# powerOutageLogger.net
KiCad netlist of a schematic drawn in EAGLE
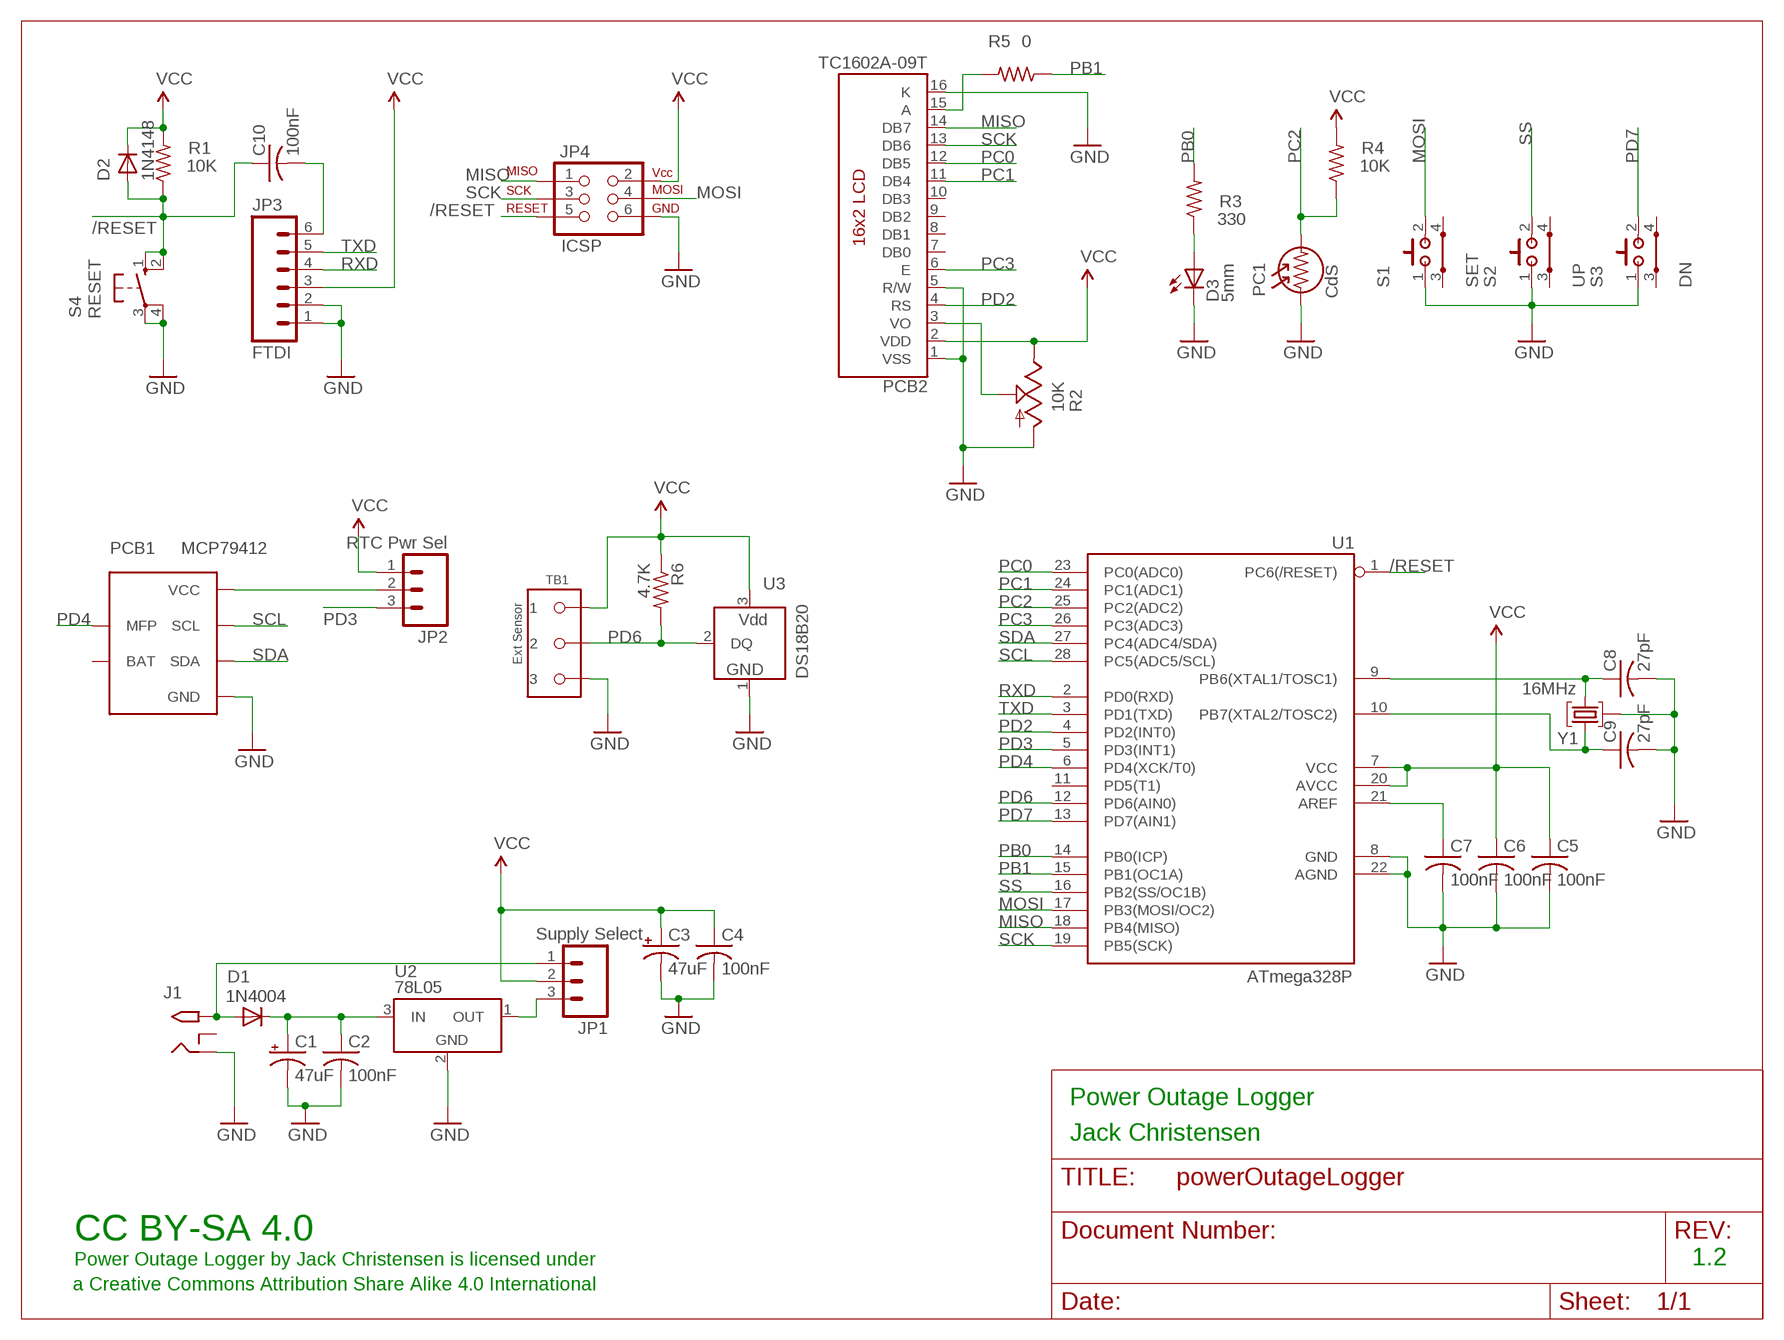
[diagram p0: schematic, sheet 1]

(export (version "E")
  (design (tool "Eeschema 10.0.6"))
  (components
    (comp (ref "C1")
      (value "47uF")
      (footprint "eagle-import:E2-5")
      (libsource (lib "eagle-import") (part "CPOL-USE2-5"))
    )
    (comp (ref "C2")
      (value "100nF")
      (footprint "eagle-import:C025-025X050")
      (libsource (lib "eagle-import") (part "C-US025-025X050"))
    )
    (comp (ref "C3")
      (value "47uF")
      (footprint "eagle-import:E2-5")
      (libsource (lib "eagle-import") (part "CPOL-USE2-5"))
    )
    (comp (ref "C4")
      (value "100nF")
      (footprint "eagle-import:C025-025X050")
      (libsource (lib "eagle-import") (part "C-US025-025X050"))
    )
    (comp (ref "C5")
      (value "100nF")
      (footprint "eagle-import:C025-025X050")
      (libsource (lib "eagle-import") (part "C-US025-025X050"))
    )
    (comp (ref "C6")
      (value "100nF")
      (footprint "eagle-import:C025-025X050")
      (libsource (lib "eagle-import") (part "C-US025-025X050"))
    )
    (comp (ref "C7")
      (value "100nF")
      (footprint "eagle-import:C025-025X050")
      (libsource (lib "eagle-import") (part "C-US025-025X050"))
    )
    (comp (ref "C8")
      (value "27pF")
      (footprint "eagle-import:C025-025X050")
      (libsource (lib "eagle-import") (part "C-US025-025X050"))
    )
    (comp (ref "C9")
      (value "27pF")
      (footprint "eagle-import:C025-025X050")
      (libsource (lib "eagle-import") (part "C-US025-025X050"))
    )
    (comp (ref "C10")
      (value "100nF")
      (footprint "eagle-import:C025-025X050")
      (libsource (lib "eagle-import") (part "C-US025-025X050"))
    )
    (comp (ref "D1")
      (value "1N4004")
      (footprint "eagle-import:1N400X")
      (libsource (lib "eagle-import") (part "DIODE1N400X"))
    )
    (comp (ref "D2")
      (value "1N4148")
      (footprint "eagle-import:1N4148")
      (libsource (lib "eagle-import") (part "DIODE1N4148"))
    )
    (comp (ref "D3")
      (value "5mm")
      (footprint "eagle-import:LED5MM")
      (libsource (lib "eagle-import") (part "LED5MM"))
    )
    (comp (ref "J1")
      (value "2.1MMJACKTHM")
      (footprint "eagle-import:PJ-102A")
      (libsource (lib "eagle-import") (part "2.1MMJACKTHM"))
    )
    (comp (ref "JP1")
      (value "Supply Select")
      (footprint "eagle-import:1X03_LOCK")
      (libsource (lib "eagle-import") (part "M03LOCK"))
    )
    (comp (ref "JP2")
      (value "RTC Pwr Sel")
      (footprint "eagle-import:1X03_LOCK")
      (libsource (lib "eagle-import") (part "M03LOCK"))
    )
    (comp (ref "JP3")
      (value "FTDI")
      (footprint "eagle-import:1X06_LOCK")
      (libsource (lib "eagle-import") (part "M06LOCK"))
    )
    (comp (ref "JP4")
      (value "ICSP")
      (footprint "eagle-import:2X3")
      (libsource (lib "eagle-import") (part "AVR_SPI_PRG_6PTH"))
    )
    (comp (ref "PC1")
      (value "CdS")
      (footprint "eagle-import:PHOTOCELL-020-017")
      (libsource (lib "eagle-import") (part "PHOTOCELL020-017"))
    )
    (comp (ref "PCB1")
      (value "MCP79412")
      (footprint "eagle-import:RTC79412")
      (libsource (lib "eagle-import") (part "RTC79412"))
    )
    (comp (ref "PCB2")
      (value "TC1602A-09T")
      (footprint "eagle-import:LCD-16X2")
      (libsource (lib "eagle-import") (part "LCD-16X2"))
    )
    (comp (ref "R1")
      (value "10K")
      (footprint "eagle-import:0204_6")
      (libsource (lib "eagle-import") (part "R-US_0204/6"))
    )
    (comp (ref "R2")
      (value "10K")
      (footprint "eagle-import:TRIMPOT-3386P")
      (libsource (lib "eagle-import") (part "TRIMPOT-3386P3386P"))
    )
    (comp (ref "R3")
      (value "330")
      (footprint "eagle-import:0204_6")
      (libsource (lib "eagle-import") (part "R-US_0204/6"))
    )
    (comp (ref "R4")
      (value "10K")
      (footprint "eagle-import:0204_6")
      (libsource (lib "eagle-import") (part "R-US_0204/6"))
    )
    (comp (ref "R5")
      (value "0")
      (footprint "eagle-import:0204_6")
      (libsource (lib "eagle-import") (part "R-US_0204/6"))
    )
    (comp (ref "R6")
      (value "4.7K")
      (footprint "eagle-import:0204_6")
      (libsource (lib "eagle-import") (part "R-US_0204/6"))
    )
    (comp (ref "S1")
      (value "SET")
      (footprint "eagle-import:B3F-312X")
      (libsource (lib "eagle-import") (part "B3F-312X"))
    )
    (comp (ref "S2")
      (value "UP")
      (footprint "eagle-import:B3F-312X")
      (libsource (lib "eagle-import") (part "B3F-312X"))
    )
    (comp (ref "S3")
      (value "DN")
      (footprint "eagle-import:B3F-312X")
      (libsource (lib "eagle-import") (part "B3F-312X"))
    )
    (comp (ref "S4")
      (value "RESET")
      (footprint "eagle-import:B3F-10XXOCT")
      (libsource (lib "eagle-import") (part "10-XXOCT"))
    )
    (comp (ref "TB1")
      (value "Ext Sensor")
      (footprint "eagle-import:OST-TB-3-3.5MM")
      (libsource (lib "eagle-import") (part "OST-TB-33.5MM"))
    )
    (comp (ref "U1")
      (value "ATmega328P")
      (footprint "eagle-import:DIL28-3")
      (libsource (lib "eagle-import") (part "AVR-MEGA8-PPTH"))
    )
    (comp (ref "U2")
      (value "78L05")
      (footprint "eagle-import:TO92-INLINE")
      (libsource (lib "eagle-import") (part "78XX-HTO92"))
    )
    (comp (ref "U3")
      (value "DS18B20")
      (footprint "eagle-import:TO92-OVAL")
      (libsource (lib "eagle-import") (part "DS18B20"))
    )
    (comp (ref "Y1")
      (value "16MHz")
      (footprint "eagle-import:RESONATOR")
      (libsource (lib "eagle-import") (part "RESONATOR"))
    )
  )
  (nets
    (net (code "1") (name "/MISO") (class "Default")
      (node (ref "JP4") (pin "1") (pinfunction "1_1") (pintype "passive"))
      (node (ref "PCB2") (pin "14") (pinfunction "DB7_14") (pintype "bidirectional"))
      (node (ref "U1") (pin "18") (pinfunction "PB4(MISO)_18") (pintype "bidirectional"))
    )
    (net (code "2") (name "/MOSI") (class "Default")
      (node (ref "JP4") (pin "4") (pinfunction "4_4") (pintype "passive"))
      (node (ref "S1") (pin "2") (pinfunction "P$2_2") (pintype "passive"))
      (node (ref "U1") (pin "17") (pinfunction "PB3(MOSI/OC2)_17") (pintype "bidirectional"))
    )
    (net (code "3") (name "/PB0") (class "Default")
      (node (ref "R3") (pin "2") (pinfunction "2_2") (pintype "passive"))
      (node (ref "U1") (pin "14") (pinfunction "PB0(ICP)_14") (pintype "bidirectional"))
    )
    (net (code "4") (name "/PB1") (class "Default")
      (node (ref "R5") (pin "1") (pinfunction "1_1") (pintype "passive"))
      (node (ref "U1") (pin "15") (pinfunction "PB1(OC1A)_15") (pintype "bidirectional"))
    )
    (net (code "5") (name "/PC0") (class "Default")
      (node (ref "PCB2") (pin "12") (pinfunction "DB5_12") (pintype "bidirectional"))
      (node (ref "U1") (pin "23") (pinfunction "PC0(ADC0)_23") (pintype "bidirectional"))
    )
    (net (code "6") (name "/PC1") (class "Default")
      (node (ref "PCB2") (pin "11") (pinfunction "DB4_11") (pintype "bidirectional"))
      (node (ref "U1") (pin "24") (pinfunction "PC1(ADC1)_24") (pintype "bidirectional"))
    )
    (net (code "7") (name "/PC2") (class "Default")
      (node (ref "PC1") (pin "P$2") (pinfunction "2_P$2") (pintype "passive"))
      (node (ref "R4") (pin "1") (pinfunction "1_1") (pintype "passive"))
      (node (ref "U1") (pin "25") (pinfunction "PC2(ADC2)_25") (pintype "bidirectional"))
    )
    (net (code "8") (name "/PC3") (class "Default")
      (node (ref "PCB2") (pin "6") (pinfunction "E_6") (pintype "input"))
      (node (ref "U1") (pin "26") (pinfunction "PC3(ADC3)_26") (pintype "bidirectional"))
    )
    (net (code "9") (name "/PD2") (class "Default")
      (node (ref "PCB2") (pin "4") (pinfunction "RS_4") (pintype "input"))
      (node (ref "U1") (pin "4") (pinfunction "PD2(INT0)_4") (pintype "bidirectional"))
    )
    (net (code "10") (name "/PD3") (class "Default")
      (node (ref "JP2") (pin "3") (pinfunction "3_3") (pintype "passive"))
      (node (ref "U1") (pin "5") (pinfunction "PD3(INT1)_5") (pintype "bidirectional"))
    )
    (net (code "11") (name "/PD4") (class "Default")
      (node (ref "PCB1") (pin "3") (pinfunction "MFP_3") (pintype "passive"))
      (node (ref "U1") (pin "6") (pinfunction "PD4(XCK/T0)_6") (pintype "bidirectional"))
    )
    (net (code "12") (name "/PD6") (class "Default")
      (node (ref "R6") (pin "2") (pinfunction "2_2") (pintype "passive"))
      (node (ref "TB1") (pin "P$2") (pinfunction "2_P$2") (pintype "passive"))
      (node (ref "U1") (pin "12") (pinfunction "PD6(AIN0)_12") (pintype "bidirectional"))
      (node (ref "U3") (pin "2") (pinfunction "DQ_2") (pintype "bidirectional"))
    )
    (net (code "13") (name "/PD7") (class "Default")
      (node (ref "S3") (pin "2") (pinfunction "P$2_2") (pintype "passive"))
      (node (ref "U1") (pin "13") (pinfunction "PD7(AIN1)_13") (pintype "bidirectional"))
    )
    (net (code "14") (name "/RXD") (class "Default")
      (node (ref "JP3") (pin "4") (pinfunction "4_4") (pintype "passive"))
      (node (ref "U1") (pin "2") (pinfunction "PD0(RXD)_2") (pintype "bidirectional"))
    )
    (net (code "15") (name "/SCK") (class "Default")
      (node (ref "JP4") (pin "3") (pinfunction "3_3") (pintype "passive"))
      (node (ref "PCB2") (pin "13") (pinfunction "DB6_13") (pintype "bidirectional"))
      (node (ref "U1") (pin "19") (pinfunction "PB5(SCK)_19") (pintype "bidirectional"))
    )
    (net (code "16") (name "/SCL") (class "Default")
      (node (ref "PCB1") (pin "6") (pinfunction "SCL_6") (pintype "passive"))
      (node (ref "U1") (pin "28") (pinfunction "PC5(ADC5/SCL)_28") (pintype "bidirectional"))
    )
    (net (code "17") (name "/SDA") (class "Default")
      (node (ref "PCB1") (pin "5") (pinfunction "SDA_5") (pintype "passive"))
      (node (ref "U1") (pin "27") (pinfunction "PC4(ADC4/SDA)_27") (pintype "bidirectional"))
    )
    (net (code "18") (name "/SS") (class "Default")
      (node (ref "S2") (pin "2") (pinfunction "P$2_2") (pintype "passive"))
      (node (ref "U1") (pin "16") (pinfunction "PB2(SS/OC1B)_16") (pintype "bidirectional"))
    )
    (net (code "19") (name "/TXD") (class "Default")
      (node (ref "JP3") (pin "5") (pinfunction "5_5") (pintype "passive"))
      (node (ref "U1") (pin "3") (pinfunction "PD1(TXD)_3") (pintype "bidirectional"))
    )
    (net (code "20") (name "/{slash}RESET") (class "Default")
      (node (ref "C10") (pin "1") (pinfunction "1_1") (pintype "passive"))
      (node (ref "D2") (pin "A") (pinfunction "A_A") (pintype "passive"))
      (node (ref "JP4") (pin "5") (pinfunction "5_5") (pintype "passive"))
      (node (ref "R1") (pin "1") (pinfunction "1_1") (pintype "passive"))
      (node (ref "S4") (pin "1") (pinfunction "S_1") (pintype "passive"))
      (node (ref "S4") (pin "2") (pinfunction "S1_2") (pintype "passive"))
      (node (ref "U1") (pin "1") (pinfunction "PC6(/RESET)_1") (pintype "bidirectional"))
    )
    (net (code "21") (name "GND") (class "Default")
      (node (ref "C1") (pin "-") (pinfunction "-_-") (pintype "passive"))
      (node (ref "C2") (pin "2") (pinfunction "2_2") (pintype "passive"))
      (node (ref "C3") (pin "-") (pinfunction "-_-") (pintype "passive"))
      (node (ref "C4") (pin "2") (pinfunction "2_2") (pintype "passive"))
      (node (ref "C5") (pin "2") (pinfunction "2_2") (pintype "passive"))
      (node (ref "C6") (pin "2") (pinfunction "2_2") (pintype "passive"))
      (node (ref "C7") (pin "2") (pinfunction "2_2") (pintype "passive"))
      (node (ref "C8") (pin "2") (pinfunction "2_2") (pintype "passive"))
      (node (ref "C9") (pin "2") (pinfunction "2_2") (pintype "passive"))
      (node (ref "D3") (pin "K") (pinfunction "C_K") (pintype "passive"))
      (node (ref "J1") (pin "RING") (pinfunction "RING_RING") (pintype "bidirectional"))
      (node (ref "JP3") (pin "1") (pinfunction "1_1") (pintype "passive"))
      (node (ref "JP3") (pin "2") (pinfunction "2_2") (pintype "passive"))
      (node (ref "JP4") (pin "6") (pinfunction "6_6") (pintype "passive"))
      (node (ref "PC1") (pin "P$1") (pinfunction "1_P$1") (pintype "passive"))
      (node (ref "PCB1") (pin "8") (pinfunction "GND_8") (pintype "passive"))
      (node (ref "PCB2") (pin "1") (pinfunction "VSS_1") (pintype "power_in"))
      (node (ref "PCB2") (pin "16") (pinfunction "K_16") (pintype "power_in"))
      (node (ref "PCB2") (pin "5") (pinfunction "R/W_5") (pintype "input"))
      (node (ref "R2") (pin "3") (pinfunction "A_3") (pintype "passive"))
      (node (ref "S1") (pin "1") (pinfunction "P$1_1") (pintype "passive"))
      (node (ref "S2") (pin "1") (pinfunction "P$1_1") (pintype "passive"))
      (node (ref "S3") (pin "1") (pinfunction "P$1_1") (pintype "passive"))
      (node (ref "S4") (pin "3") (pinfunction "P_3") (pintype "passive"))
      (node (ref "S4") (pin "4") (pinfunction "P1_4") (pintype "passive"))
      (node (ref "TB1") (pin "P$3") (pinfunction "3_P$3") (pintype "passive"))
      (node (ref "U1") (pin "22") (pinfunction "AGND_22") (pintype "bidirectional"))
      (node (ref "U1") (pin "8") (pinfunction "GND_8") (pintype "bidirectional"))
      (node (ref "U2") (pin "2") (pinfunction "GND_2") (pintype "power_in"))
      (node (ref "U3") (pin "1") (pinfunction "GND_1") (pintype "bidirectional"))
      (node (ref "Y1") (pin "2") (pinfunction "2_2") (pintype "passive"))
    )
    (net (code "22") (name "Net-(C10-Pad2)") (class "Default")
      (node (ref "C10") (pin "2") (pinfunction "2_2") (pintype "passive"))
      (node (ref "JP3") (pin "6") (pinfunction "6_6") (pintype "passive"))
    )
    (net (code "23") (name "Net-(D1-PadA)") (class "Default")
      (node (ref "D1") (pin "A") (pinfunction "A_A") (pintype "passive"))
      (node (ref "J1") (pin "TIP") (pinfunction "TIP_TIP") (pintype "bidirectional"))
      (node (ref "JP1") (pin "1") (pinfunction "1_1") (pintype "passive"))
    )
    (net (code "24") (name "Net-(D3-PadA)") (class "Default")
      (node (ref "D3") (pin "A") (pinfunction "A_A") (pintype "passive"))
      (node (ref "R3") (pin "1") (pinfunction "1_1") (pintype "passive"))
    )
    (net (code "25") (name "Net-(PCB1-VCC)") (class "Default")
      (node (ref "JP2") (pin "2") (pinfunction "2_2") (pintype "passive"))
      (node (ref "PCB1") (pin "7") (pinfunction "VCC_7") (pintype "passive"))
    )
    (net (code "26") (name "Net-(PCB2-A)") (class "Default")
      (node (ref "PCB2") (pin "15") (pinfunction "A_15") (pintype "power_in"))
      (node (ref "R5") (pin "2") (pinfunction "2_2") (pintype "passive"))
    )
    (net (code "27") (name "Net-(PCB2-VO)") (class "Default")
      (node (ref "PCB2") (pin "3") (pinfunction "VO_3") (pintype "bidirectional"))
      (node (ref "R2") (pin "2") (pinfunction "S_2") (pintype "passive"))
    )
    (net (code "28") (name "Net-(U1-AREF)") (class "Default")
      (node (ref "C7") (pin "1") (pinfunction "1_1") (pintype "passive"))
      (node (ref "U1") (pin "21") (pinfunction "AREF_21") (pintype "bidirectional"))
    )
    (net (code "29") (name "Net-(U1-PB6(XTAL1{slash}TOSC1))") (class "Default")
      (node (ref "C8") (pin "1") (pinfunction "1_1") (pintype "passive"))
      (node (ref "U1") (pin "9") (pinfunction "PB6(XTAL1/TOSC1)_9") (pintype "bidirectional"))
      (node (ref "Y1") (pin "3") (pinfunction "3_3") (pintype "passive"))
    )
    (net (code "30") (name "Net-(U1-PB7(XTAL2{slash}TOSC2))") (class "Default")
      (node (ref "C9") (pin "1") (pinfunction "1_1") (pintype "passive"))
      (node (ref "U1") (pin "10") (pinfunction "PB7(XTAL2/TOSC2)_10") (pintype "bidirectional"))
      (node (ref "Y1") (pin "1") (pinfunction "1_1") (pintype "passive"))
    )
    (net (code "31") (name "Net-(U2-IN)") (class "Default")
      (node (ref "C1") (pin "+") (pinfunction "+_+") (pintype "passive"))
      (node (ref "C2") (pin "1") (pinfunction "1_1") (pintype "passive"))
      (node (ref "D1") (pin "K") (pinfunction "K_K") (pintype "passive"))
      (node (ref "U2") (pin "3") (pinfunction "IN_3") (pintype "input"))
    )
    (net (code "32") (name "Net-(U2-OUT)") (class "Default")
      (node (ref "JP1") (pin "3") (pinfunction "3_3") (pintype "passive"))
      (node (ref "U2") (pin "1") (pinfunction "OUT_1") (pintype "power_in"))
    )
    (net (code "33") (name "VCC") (class "Default")
      (node (ref "C3") (pin "+") (pinfunction "+_+") (pintype "passive"))
      (node (ref "C4") (pin "1") (pinfunction "1_1") (pintype "passive"))
      (node (ref "C5") (pin "1") (pinfunction "1_1") (pintype "passive"))
      (node (ref "C6") (pin "1") (pinfunction "1_1") (pintype "passive"))
      (node (ref "D2") (pin "K") (pinfunction "K_K") (pintype "passive"))
      (node (ref "JP1") (pin "2") (pinfunction "2_2") (pintype "passive"))
      (node (ref "JP2") (pin "1") (pinfunction "1_1") (pintype "passive"))
      (node (ref "JP3") (pin "3") (pinfunction "3_3") (pintype "passive"))
      (node (ref "JP4") (pin "2") (pinfunction "2_2") (pintype "passive"))
      (node (ref "PCB2") (pin "2") (pinfunction "VDD_2") (pintype "power_in"))
      (node (ref "R1") (pin "2") (pinfunction "2_2") (pintype "passive"))
      (node (ref "R2") (pin "1") (pinfunction "E_1") (pintype "passive"))
      (node (ref "R4") (pin "2") (pinfunction "2_2") (pintype "passive"))
      (node (ref "R6") (pin "1") (pinfunction "1_1") (pintype "passive"))
      (node (ref "TB1") (pin "P$1") (pinfunction "1_P$1") (pintype "passive"))
      (node (ref "U1") (pin "20") (pinfunction "AVCC_20") (pintype "bidirectional"))
      (node (ref "U1") (pin "7") (pinfunction "VCC_7") (pintype "bidirectional"))
      (node (ref "U3") (pin "3") (pinfunction "VDD_3") (pintype "bidirectional"))
    )
    (net (code "34") (name "unconnected-(J1-PadRING_SW)") (class "Default")
      (node (ref "J1") (pin "RING_SW") (pinfunction "RING_SW_RING_SW") (pintype "bidirectional"))
    )
    (net (code "35") (name "unconnected-(PCB1-BAT-Pad1)") (class "Default")
      (node (ref "PCB1") (pin "1") (pinfunction "BAT_1") (pintype "passive"))
    )
    (net (code "36") (name "unconnected-(PCB2-DB0-Pad7)") (class "Default")
      (node (ref "PCB2") (pin "7") (pinfunction "DB0_7") (pintype "bidirectional"))
    )
    (net (code "37") (name "unconnected-(PCB2-DB1-Pad8)") (class "Default")
      (node (ref "PCB2") (pin "8") (pinfunction "DB1_8") (pintype "bidirectional"))
    )
    (net (code "38") (name "unconnected-(PCB2-DB2-Pad9)") (class "Default")
      (node (ref "PCB2") (pin "9") (pinfunction "DB2_9") (pintype "bidirectional"))
    )
    (net (code "39") (name "unconnected-(PCB2-DB3-Pad10)") (class "Default")
      (node (ref "PCB2") (pin "10") (pinfunction "DB3_10") (pintype "bidirectional"))
    )
    (net (code "40") (name "unconnected-(S1-P$3-Pad3)") (class "Default")
      (node (ref "S1") (pin "3") (pinfunction "P$3_3") (pintype "passive"))
    )
    (net (code "41") (name "unconnected-(S1-P$4-Pad4)") (class "Default")
      (node (ref "S1") (pin "4") (pinfunction "P$4_4") (pintype "passive"))
    )
    (net (code "42") (name "unconnected-(S2-P$3-Pad3)") (class "Default")
      (node (ref "S2") (pin "3") (pinfunction "P$3_3") (pintype "passive"))
    )
    (net (code "43") (name "unconnected-(S2-P$4-Pad4)") (class "Default")
      (node (ref "S2") (pin "4") (pinfunction "P$4_4") (pintype "passive"))
    )
    (net (code "44") (name "unconnected-(S3-P$3-Pad3)") (class "Default")
      (node (ref "S3") (pin "3") (pinfunction "P$3_3") (pintype "passive"))
    )
    (net (code "45") (name "unconnected-(S3-P$4-Pad4)") (class "Default")
      (node (ref "S3") (pin "4") (pinfunction "P$4_4") (pintype "passive"))
    )
    (net (code "46") (name "unconnected-(U1-PD5(T1)-Pad11)") (class "Default")
      (node (ref "U1") (pin "11") (pinfunction "PD5(T1)_11") (pintype "bidirectional"))
    )
  )
)
